# Voltage_Regulator.net
KiCad netlist of a schematic drawn in EAGLE
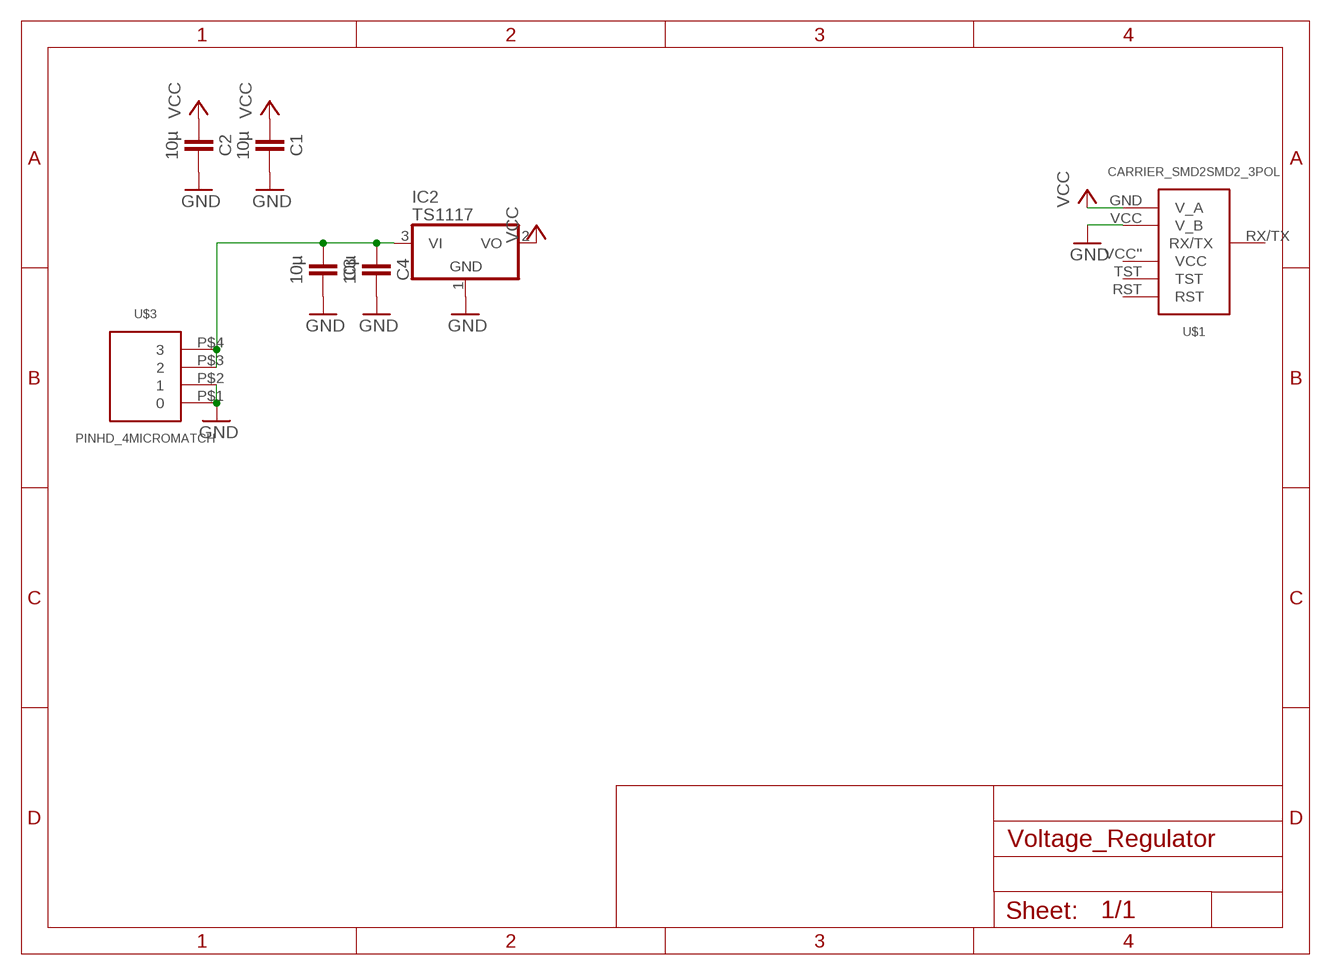
[diagram p0: schematic, sheet 1]

(export (version "E")
  (design (tool "Eeschema 10.0.6"))
  (components
    (comp (ref "C1")
      (value "10µ")
      (footprint "eagle-import:603")
      (libsource (lib "eagle-import") (part "CAPACITOR"))
    )
    (comp (ref "C2")
      (value "10µ")
      (footprint "eagle-import:603")
      (libsource (lib "eagle-import") (part "CAPACITOR"))
    )
    (comp (ref "C3")
      (value "10µ")
      (footprint "eagle-import:603")
      (libsource (lib "eagle-import") (part "CAPACITOR"))
    )
    (comp (ref "C4")
      (value "10µ")
      (footprint "eagle-import:603")
      (libsource (lib "eagle-import") (part "CAPACITOR"))
    )
    (comp (ref "IC2")
      (value "TS1117")
      (footprint "eagle-import:SOT223")
      (libsource (lib "eagle-import") (part "TS1117"))
    )
    (comp (ref "U$1")
      (value "CARRIER_SMD2SMD2_3POL")
      (footprint "eagle-import:CARRIER_SMD2_3POL")
      (libsource (lib "eagle-import") (part "CARRIER_SMD2SMD2_3POL"))
    )
    (comp (ref "U$3")
      (value "PINHD_4MICROMATCH")
      (footprint "eagle-import:MICROMATCH4P0L")
      (libsource (lib "eagle-import") (part "PINHD_4MICROMATCH"))
    )
  )
  (nets
    (net (code "1") (name "GND") (class "Default")
      (node (ref "C1") (pin "2") (pinfunction "2_2") (pintype "passive"))
      (node (ref "C2") (pin "2") (pinfunction "2_2") (pintype "passive"))
      (node (ref "C3") (pin "2") (pinfunction "2_2") (pintype "passive"))
      (node (ref "C4") (pin "2") (pinfunction "2_2") (pintype "passive"))
      (node (ref "IC2") (pin "1") (pinfunction "GND_1") (pintype "passive"))
      (node (ref "U$1") (pin "VCC") (pinfunction "V_B_VCC") (pintype "bidirectional"))
      (node (ref "U$3") (pin "P$1") (pinfunction "0_P$1") (pintype "bidirectional"))
      (node (ref "U$3") (pin "P$2") (pinfunction "1_P$2") (pintype "bidirectional"))
    )
    (net (code "2") (name "Net-(IC2-VI)") (class "Default")
      (node (ref "C3") (pin "1") (pinfunction "1_1") (pintype "passive"))
      (node (ref "C4") (pin "1") (pinfunction "1_1") (pintype "passive"))
      (node (ref "IC2") (pin "3") (pinfunction "VI_3") (pintype "input"))
      (node (ref "U$3") (pin "P$3") (pinfunction "2_P$3") (pintype "bidirectional"))
      (node (ref "U$3") (pin "P$4") (pinfunction "3_P$4") (pintype "bidirectional"))
    )
    (net (code "3") (name "VCC") (class "Default")
      (node (ref "C1") (pin "1") (pinfunction "1_1") (pintype "passive"))
      (node (ref "C2") (pin "1") (pinfunction "1_1") (pintype "passive"))
      (node (ref "IC2") (pin "2") (pinfunction "VO_2") (pintype "passive"))
      (node (ref "U$1") (pin "GND") (pinfunction "V_A_GND") (pintype "bidirectional"))
    )
    (net (code "4") (name "unconnected-(U$1-PadRST)") (class "Default")
      (node (ref "U$1") (pin "RST") (pinfunction "RST_RST") (pintype "bidirectional"))
    )
    (net (code "5") (name "unconnected-(U$1-PadRX{slash}TX)") (class "Default")
      (node (ref "U$1") (pin "RX/TX") (pinfunction "RX/TX_RX/TX") (pintype "bidirectional"))
    )
    (net (code "6") (name "unconnected-(U$1-PadTST)") (class "Default")
      (node (ref "U$1") (pin "TST") (pinfunction "TST_TST") (pintype "bidirectional"))
    )
    (net (code "7") (name "unconnected-(U$1-VCC-PadVCC'')") (class "Default")
      (node (ref "U$1") (pin "VCC''") (pinfunction "VCC_VCC''") (pintype "bidirectional"))
    )
  )
)
